# Battery_board_V4_1.net
KiCad netlist of a schematic drawn in EAGLE
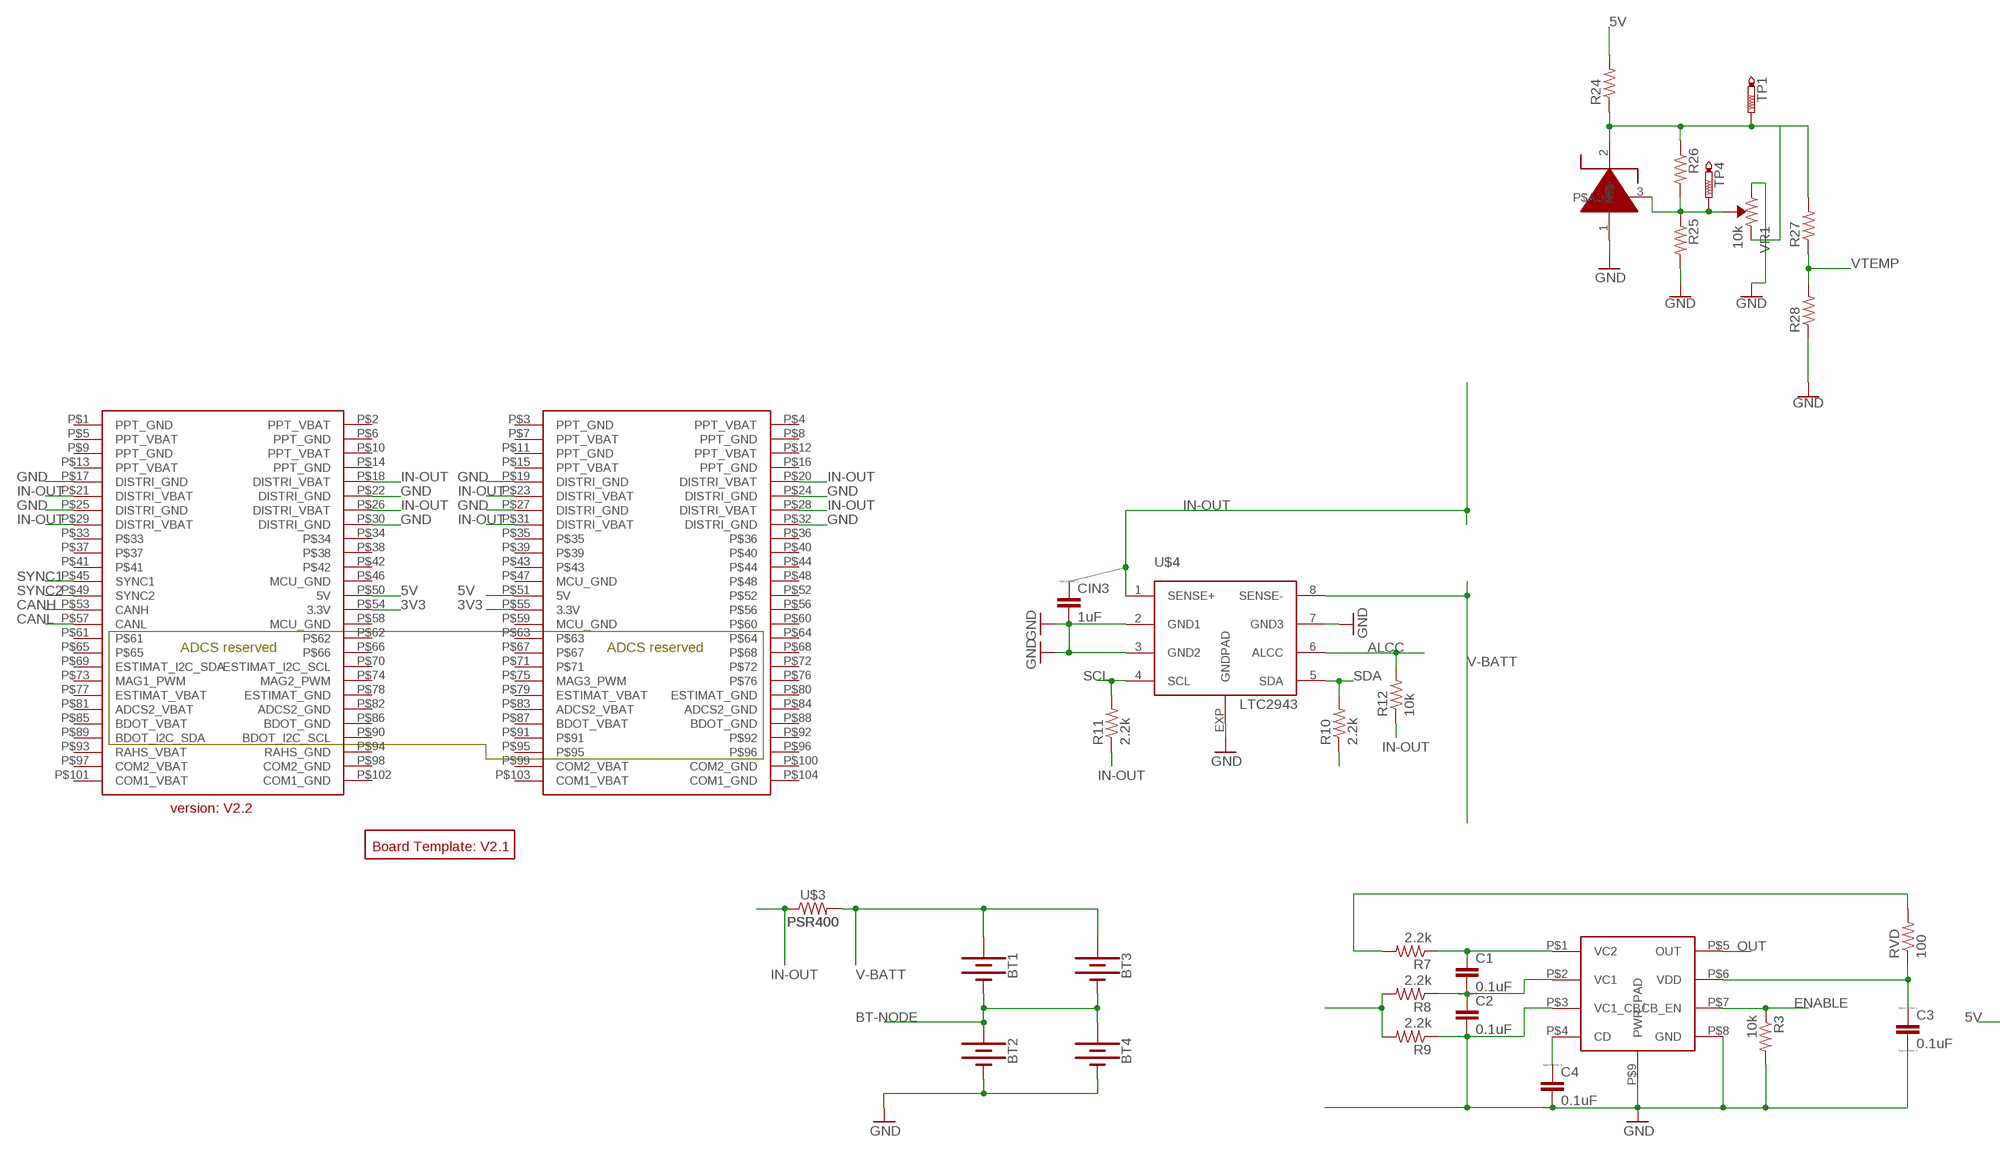
[diagram p0: schematic, sheet 1, part 1 of 2]
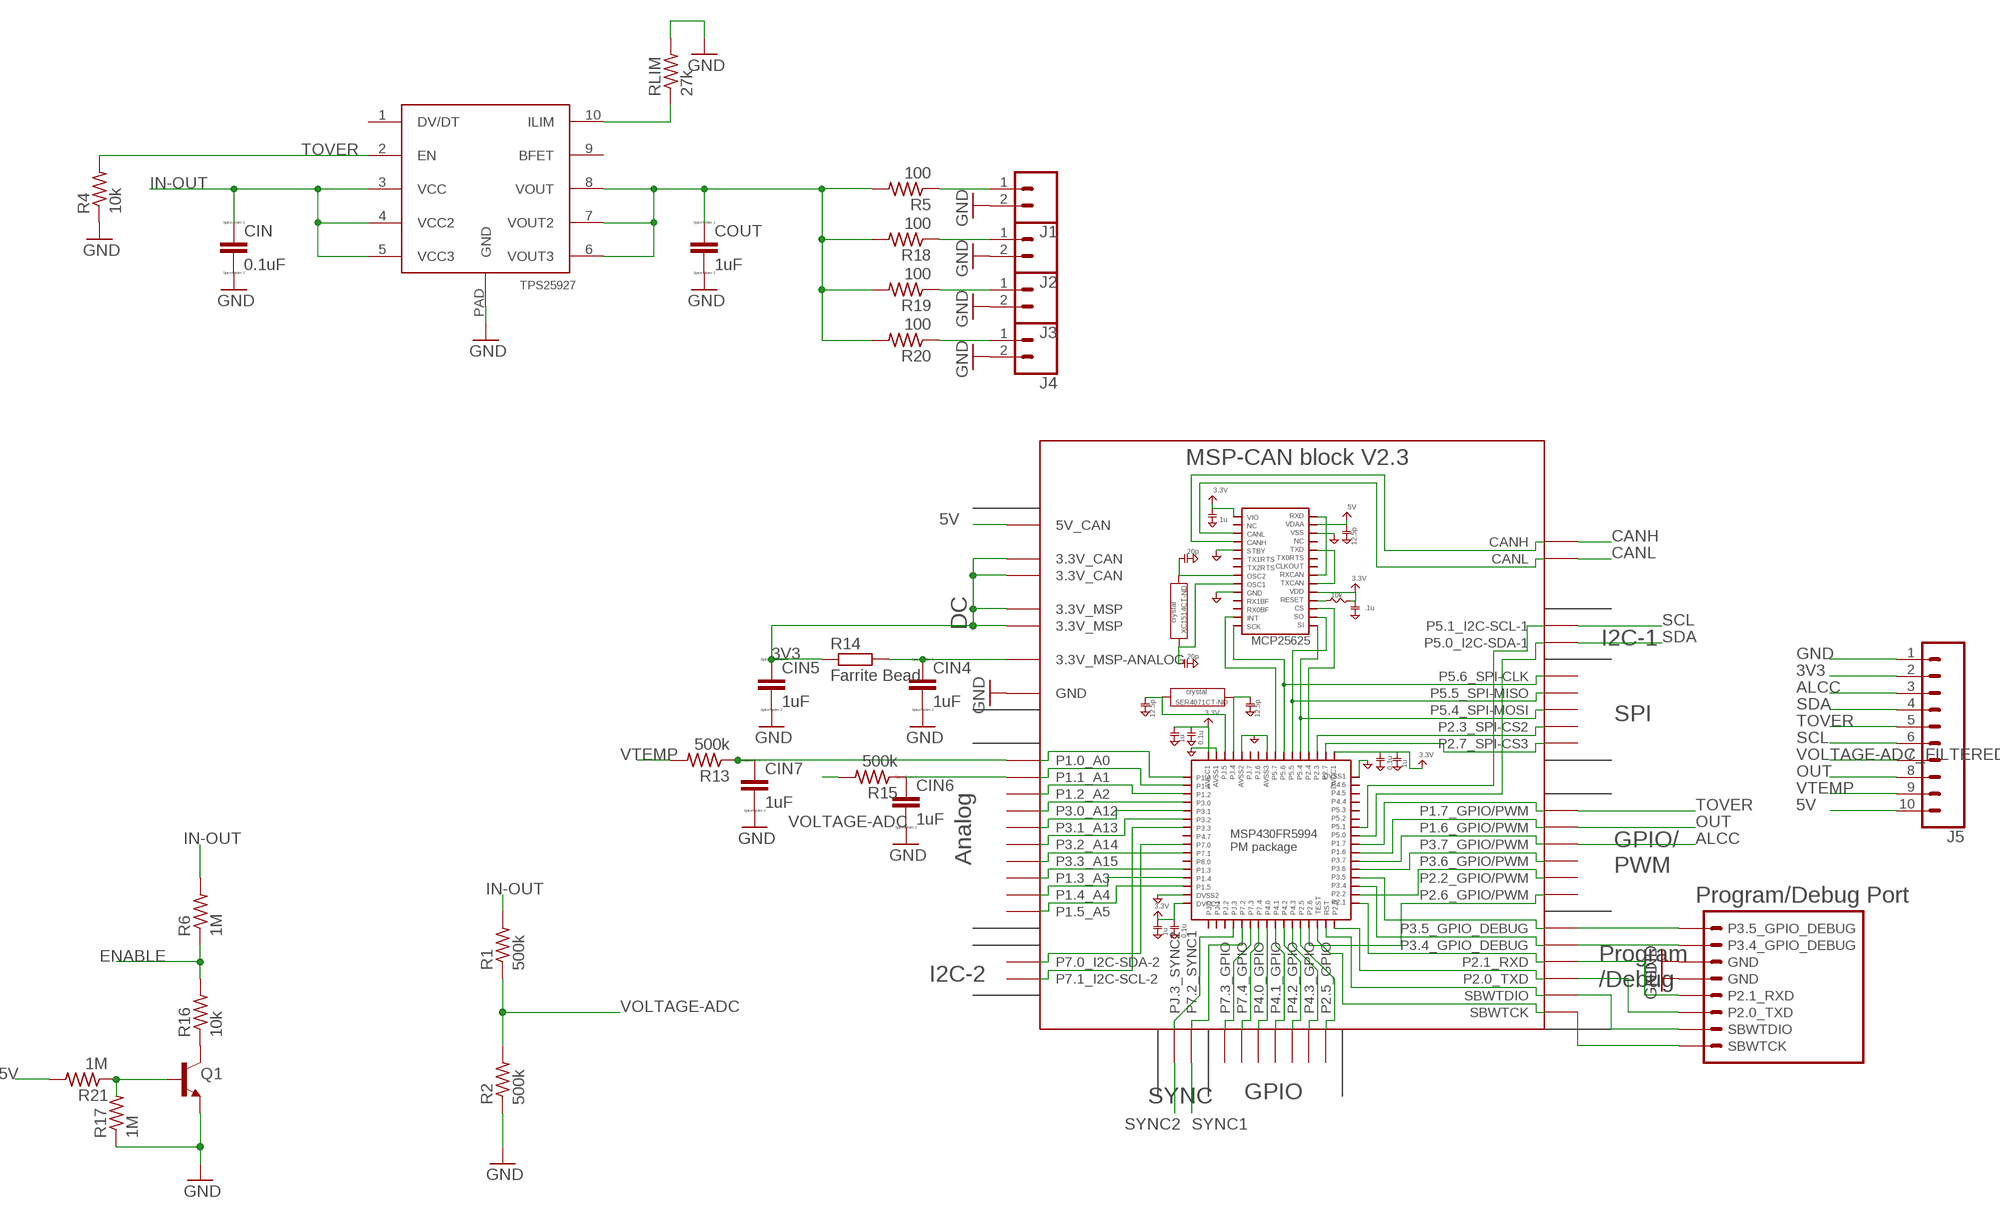
[diagram p1: schematic, sheet 1, part 2 of 2]

(export (version "E")
  (design (tool "Eeschema 10.0.6"))
  (components
    (comp (ref "BT1")
      (value "BATTERY-18650")
      (footprint "eagle-import:BATTERY_18650-HOLDER")
      (libsource (lib "eagle-import") (part "BATTERY-18650"))
    )
    (comp (ref "BT2")
      (value "BATTERY-18650")
      (footprint "eagle-import:BATTERY_18650-HOLDER")
      (libsource (lib "eagle-import") (part "BATTERY-18650"))
    )
    (comp (ref "BT3")
      (value "BATTERY-18650")
      (footprint "eagle-import:BATTERY_18650-HOLDER")
      (libsource (lib "eagle-import") (part "BATTERY-18650"))
    )
    (comp (ref "BT4")
      (value "BATTERY-18650")
      (footprint "eagle-import:BATTERY_18650-HOLDER")
      (libsource (lib "eagle-import") (part "BATTERY-18650"))
    )
    (comp (ref "C1")
      (value "0.1uF")
      (footprint "eagle-import:C0805")
      (libsource (lib "eagle-import") (part "C"))
    )
    (comp (ref "C2")
      (value "0.1uF")
      (footprint "eagle-import:C0805")
      (libsource (lib "eagle-import") (part "C"))
    )
    (comp (ref "C3")
      (value "0.1uF")
      (footprint "eagle-import:C0805")
      (libsource (lib "eagle-import") (part "C"))
    )
    (comp (ref "C4")
      (value "0.1uF")
      (footprint "eagle-import:C0805")
      (libsource (lib "eagle-import") (part "C"))
    )
    (comp (ref "CIN")
      (value "0.1uF")
      (footprint "eagle-import:C0805")
      (libsource (lib "eagle-import") (part "C"))
    )
    (comp (ref "CIN3")
      (value "1uF")
      (footprint "eagle-import:C0805")
      (libsource (lib "eagle-import") (part "C"))
    )
    (comp (ref "CIN4")
      (value "1uF")
      (footprint "eagle-import:C0805")
      (libsource (lib "eagle-import") (part "C"))
    )
    (comp (ref "CIN5")
      (value "1uF")
      (footprint "eagle-import:C0805")
      (libsource (lib "eagle-import") (part "C"))
    )
    (comp (ref "CIN6")
      (value "1uF")
      (footprint "eagle-import:C0805")
      (libsource (lib "eagle-import") (part "C"))
    )
    (comp (ref "CIN7")
      (value "1uF")
      (footprint "eagle-import:C0805")
      (libsource (lib "eagle-import") (part "C"))
    )
    (comp (ref "COUT")
      (value "1uF")
      (footprint "eagle-import:C0805")
      (libsource (lib "eagle-import") (part "C"))
    )
    (comp (ref "J1")
      (value "CONN_02PTH3")
      (footprint "eagle-import:1X02_LONGPADS")
      (libsource (lib "eagle-import") (part "CONN_02PTH3"))
    )
    (comp (ref "J2")
      (value "CONN_02PTH3")
      (footprint "eagle-import:1X02_LONGPADS")
      (libsource (lib "eagle-import") (part "CONN_02PTH3"))
    )
    (comp (ref "J3")
      (value "CONN_02PTH3")
      (footprint "eagle-import:1X02_LONGPADS")
      (libsource (lib "eagle-import") (part "CONN_02PTH3"))
    )
    (comp (ref "J4")
      (value "CONN_02PTH3")
      (footprint "eagle-import:1X02_LONGPADS")
      (libsource (lib "eagle-import") (part "CONN_02PTH3"))
    )
    (comp (ref "J5")
      (value "CONN_10LOCK")
      (footprint "eagle-import:1X10_LOCK")
      (libsource (lib "eagle-import") (part "CONN_10LOCK"))
    )
    (comp (ref "Q1")
      (value "TRANS_NPN-MMBT2222AL")
      (footprint "eagle-import:SOT23-3")
      (libsource (lib "eagle-import") (part "TRANS_NPN-MMBT2222AL"))
    )
    (comp (ref "R1")
      (value "500k")
      (footprint "eagle-import:R0805")
      (libsource (lib "eagle-import") (part "R-US_R0805"))
    )
    (comp (ref "R2")
      (value "500k")
      (footprint "eagle-import:R0805")
      (libsource (lib "eagle-import") (part "R-US_R0805"))
    )
    (comp (ref "R3")
      (value "10k")
      (footprint "eagle-import:R0805")
      (libsource (lib "eagle-import") (part "R-US_R0805"))
    )
    (comp (ref "R4")
      (value "10k")
      (footprint "eagle-import:R0805")
      (libsource (lib "eagle-import") (part "R-US_R0805"))
    )
    (comp (ref "R5")
      (value "100")
      (footprint "eagle-import:R0805")
      (libsource (lib "eagle-import") (part "R-US_R0805"))
    )
    (comp (ref "R6")
      (value "1M")
      (footprint "eagle-import:R0805")
      (libsource (lib "eagle-import") (part "R-US_R0805"))
    )
    (comp (ref "R7")
      (value "2.2k")
      (footprint "eagle-import:R0805")
      (libsource (lib "eagle-import") (part "R-US_R0805"))
    )
    (comp (ref "R8")
      (value "2.2k")
      (footprint "eagle-import:R0805")
      (libsource (lib "eagle-import") (part "R-US_R0805"))
    )
    (comp (ref "R9")
      (value "2.2k")
      (footprint "eagle-import:R0805")
      (libsource (lib "eagle-import") (part "R-US_R0805"))
    )
    (comp (ref "R10")
      (value "2.2k")
      (footprint "eagle-import:R0805")
      (libsource (lib "eagle-import") (part "R-US_R0805"))
    )
    (comp (ref "R11")
      (value "2.2k")
      (footprint "eagle-import:R0805")
      (libsource (lib "eagle-import") (part "R-US_R0805"))
    )
    (comp (ref "R12")
      (value "10k")
      (footprint "eagle-import:R0805")
      (libsource (lib "eagle-import") (part "R-US_R0805"))
    )
    (comp (ref "R13")
      (value "500k")
      (footprint "eagle-import:R0805")
      (libsource (lib "eagle-import") (part "R-US_R0805"))
    )
    (comp (ref "R14")
      (value "Farrite Bead")
      (footprint "eagle-import:R1206")
      (libsource (lib "eagle-import") (part "R-EU_R1206"))
    )
    (comp (ref "R15")
      (value "500k")
      (footprint "eagle-import:R0805")
      (libsource (lib "eagle-import") (part "R-US_R0805"))
    )
    (comp (ref "R16")
      (value "10k")
      (footprint "eagle-import:R0805")
      (libsource (lib "eagle-import") (part "R-US_R0805"))
    )
    (comp (ref "R17")
      (value "1M")
      (footprint "eagle-import:M0805")
      (libsource (lib "eagle-import") (part "R-US_M0805"))
    )
    (comp (ref "R18")
      (value "100")
      (footprint "eagle-import:R0805")
      (libsource (lib "eagle-import") (part "R-US_R0805"))
    )
    (comp (ref "R19")
      (value "100")
      (footprint "eagle-import:R0805")
      (libsource (lib "eagle-import") (part "R-US_R0805"))
    )
    (comp (ref "R20")
      (value "100")
      (footprint "eagle-import:R0805")
      (libsource (lib "eagle-import") (part "R-US_R0805"))
    )
    (comp (ref "R21")
      (value "1M")
      (footprint "eagle-import:M0805")
      (libsource (lib "eagle-import") (part "R-US_M0805"))
    )
    (comp (ref "R24")
      (value "R-US_R0805")
      (footprint "eagle-import:R0805")
      (libsource (lib "eagle-import") (part "R-US_R0805"))
    )
    (comp (ref "R25")
      (value "R-US_R0805")
      (footprint "eagle-import:R0805")
      (libsource (lib "eagle-import") (part "R-US_R0805"))
    )
    (comp (ref "R26")
      (value "R-US_R0805")
      (footprint "eagle-import:R0805")
      (libsource (lib "eagle-import") (part "R-US_R0805"))
    )
    (comp (ref "R27")
      (value "R-US_R0805")
      (footprint "eagle-import:R0805")
      (libsource (lib "eagle-import") (part "R-US_R0805"))
    )
    (comp (ref "R28")
      (value "R-US_R0805")
      (footprint "eagle-import:R0805")
      (libsource (lib "eagle-import") (part "R-US_R0805"))
    )
    (comp (ref "RLIM")
      (value "27k")
      (footprint "eagle-import:R0805")
      (libsource (lib "eagle-import") (part "R-US_R0805"))
    )
    (comp (ref "RVD")
      (value "100")
      (footprint "eagle-import:R0805")
      (libsource (lib "eagle-import") (part "R-US_R0805"))
    )
    (comp (ref "TP1")
      (value "PTR1PAD1-13Y")
      (footprint "eagle-import:P1-13Y")
      (libsource (lib "eagle-import") (part "PTR1PAD1-13Y"))
    )
    (comp (ref "TP4")
      (value "PTR1PAD1-13Y")
      (footprint "eagle-import:P1-13Y")
      (libsource (lib "eagle-import") (part "PTR1PAD1-13Y"))
    )
    (comp (ref "U$1")
      (value "MSP-CAN_BLOCK")
      (footprint "eagle-import:MSP-CAN_BLOCK")
      (libsource (lib "eagle-import") (part "MSP-CAN_BLOCK"))
    )
    (comp (ref "U$2")
      (value "PROGRAM/DEBUG_PORT")
      (footprint "eagle-import:1X08_CONNECTOR")
      (libsource (lib "eagle-import") (part "PROGRAM/DEBUG_PORT"))
    )
    (comp (ref "U$3")
      (value "PSR400")
      (footprint "eagle-import:PSR400")
      (libsource (lib "eagle-import") (part "PSR400"))
    )
    (comp (ref "U$4")
      (value "LTC2943")
      (footprint "eagle-import:DFN8(3X3)LT")
      (libsource (lib "eagle-import") (part "LTC2943"))
    )
    (comp (ref "U$5")
      (value "TPS252927")
      (footprint "eagle-import:VSON10")
      (libsource (lib "eagle-import") (part "TPS252927"))
    )
    (comp (ref "U$7")
      (value "2X26_CONNECTOR_(V2.2)")
      (footprint "eagle-import:4X26_CONNECTOR_(V2.2)")
      (libsource (lib "eagle-import") (part "2X26_CONNECTOR_(V2.2)"))
    )
    (comp (ref "U$8")
      (value "BQ29209")
      (footprint "eagle-import:VSON8")
      (libsource (lib "eagle-import") (part "BQ29209"))
    )
    (comp (ref "U$9")
      (value "BOARD_TEMPLATE_(V2.1)")
      (footprint "eagle-import:BOARD_TEMPLATE_(V2.1)")
      (libsource (lib "eagle-import") (part "BOARD_TEMPLATE_(V2.1)"))
    )
    (comp (ref "U$10")
      (value "LM135Z")
      (footprint "eagle-import:TO-92-3")
      (libsource (lib "eagle-import") (part "LM135Z"))
    )
    (comp (ref "VR1")
      (value "10k")
      (footprint "eagle-import:TRIMPOT-SMD-TC33X")
      (libsource (lib "eagle-import") (part "TRIMPOT-SMD-3MM-OPEN-1/10W-25%"))
    )
  )
  (nets
    (net (code "1") (name "/3V3") (class "Default")
      (node (ref "CIN5") (pin "1") (pinfunction "1_1") (pintype "passive"))
      (node (ref "J5") (pin "2") (pinfunction "2_2") (pintype "passive"))
      (node (ref "R14") (pin "1") (pinfunction "1_1") (pintype "passive"))
      (node (ref "U$1") (pin "3.3V@CAN1") (pinfunction "3.3V_CAN_3.3V@CAN1") (pintype "bidirectional"))
      (node (ref "U$1") (pin "3.3V@CAN2") (pinfunction "3.3V_CAN_3.3V@CAN2") (pintype "bidirectional"))
      (node (ref "U$1") (pin "3.3V@MSP1") (pinfunction "3.3V_MSP_3.3V@MSP1") (pintype "bidirectional"))
      (node (ref "U$1") (pin "3.3V@MSP2") (pinfunction "3.3V_MSP_3.3V@MSP2") (pintype "bidirectional"))
      (node (ref "U$7") (pin "P$54") (pinfunction "3.3V_P$54") (pintype "bidirectional"))
      (node (ref "U$7") (pin "P$55") (pinfunction "3.3V_P$55") (pintype "bidirectional"))
    )
    (net (code "2") (name "/5V") (class "Default")
      (node (ref "J5") (pin "10") (pinfunction "10_10") (pintype "passive"))
      (node (ref "R21") (pin "2") (pinfunction "2_2") (pintype "passive"))
      (node (ref "R24") (pin "2") (pinfunction "2_2") (pintype "passive"))
      (node (ref "U$1") (pin "5V") (pinfunction "5V_CAN_5V") (pintype "bidirectional"))
      (node (ref "U$7") (pin "P$50") (pinfunction "5V_P$50") (pintype "bidirectional"))
      (node (ref "U$7") (pin "P$51") (pinfunction "5V_P$51") (pintype "bidirectional"))
    )
    (net (code "3") (name "/ALCC") (class "Default")
      (node (ref "J5") (pin "3") (pinfunction "3_3") (pintype "passive"))
      (node (ref "R12") (pin "2") (pinfunction "2_2") (pintype "passive"))
      (node (ref "U$1") (pin "P3.7_GPIO/PWM") (pinfunction "P3.7_GPIO/PWM_P3.7_GPIO/PWM") (pintype "bidirectional"))
      (node (ref "U$4") (pin "6") (pinfunction "ALCC_6") (pintype "bidirectional"))
    )
    (net (code "4") (name "/BT-NODE") (class "Default")
      (node (ref "BT1") (pin "GND@1") (pinfunction "-_GND@1") (pintype "power_in"))
      (node (ref "BT2") (pin "PWR@1") (pinfunction "+_PWR@1") (pintype "power_in"))
      (node (ref "BT3") (pin "GND@1") (pinfunction "-_GND@1") (pintype "power_in"))
      (node (ref "BT4") (pin "PWR@1") (pinfunction "+_PWR@1") (pintype "power_in"))
      (node (ref "R8") (pin "2") (pinfunction "2_2") (pintype "passive"))
      (node (ref "R9") (pin "2") (pinfunction "2_2") (pintype "passive"))
    )
    (net (code "5") (name "/CANH") (class "Default")
      (node (ref "U$1") (pin "CANH") (pinfunction "CANH_CANH") (pintype "bidirectional"))
      (node (ref "U$7") (pin "P$53") (pinfunction "CANH_P$53") (pintype "bidirectional"))
    )
    (net (code "6") (name "/CANL") (class "Default")
      (node (ref "U$1") (pin "CANL") (pinfunction "CANL_CANL") (pintype "bidirectional"))
      (node (ref "U$7") (pin "P$57") (pinfunction "CANL_P$57") (pintype "bidirectional"))
    )
    (net (code "7") (name "/ENABLE") (class "Default")
      (node (ref "R16") (pin "2") (pinfunction "2_2") (pintype "passive"))
      (node (ref "R3") (pin "1") (pinfunction "1_1") (pintype "passive"))
      (node (ref "R6") (pin "1") (pinfunction "1_1") (pintype "passive"))
      (node (ref "U$8") (pin "P$7") (pinfunction "CB_EN_P$7") (pintype "bidirectional"))
    )
    (net (code "8") (name "/IN-OUT") (class "Default")
      (node (ref "CIN") (pin "1") (pinfunction "1_1") (pintype "passive"))
      (node (ref "CIN3") (pin "1") (pinfunction "1_1") (pintype "passive"))
      (node (ref "R1") (pin "2") (pinfunction "2_2") (pintype "passive"))
      (node (ref "R10") (pin "1") (pinfunction "1_1") (pintype "passive"))
      (node (ref "R11") (pin "1") (pinfunction "1_1") (pintype "passive"))
      (node (ref "R12") (pin "1") (pinfunction "1_1") (pintype "passive"))
      (node (ref "R6") (pin "2") (pinfunction "2_2") (pintype "passive"))
      (node (ref "R7") (pin "2") (pinfunction "2_2") (pintype "passive"))
      (node (ref "RVD") (pin "2") (pinfunction "2_2") (pintype "passive"))
      (node (ref "U$3") (pin "P$1") (pinfunction "1_P$1") (pintype "passive"))
      (node (ref "U$4") (pin "1") (pinfunction "SENSE+_1") (pintype "bidirectional"))
      (node (ref "U$5") (pin "3") (pinfunction "VCC_3") (pintype "bidirectional"))
      (node (ref "U$5") (pin "4") (pinfunction "VCC2_4") (pintype "bidirectional"))
      (node (ref "U$5") (pin "5") (pinfunction "VCC3_5") (pintype "bidirectional"))
      (node (ref "U$7") (pin "P$18") (pinfunction "DISTRI_VBAT_P$18") (pintype "bidirectional"))
      (node (ref "U$7") (pin "P$20") (pinfunction "DISTRI_VBAT_P$20") (pintype "bidirectional"))
      (node (ref "U$7") (pin "P$21") (pinfunction "DISTRI_VBAT_P$21") (pintype "bidirectional"))
      (node (ref "U$7") (pin "P$23") (pinfunction "DISTRI_VBAT_P$23") (pintype "bidirectional"))
      (node (ref "U$7") (pin "P$26") (pinfunction "DISTRI_VBAT_P$26") (pintype "bidirectional"))
      (node (ref "U$7") (pin "P$28") (pinfunction "DISTRI_VBAT_P$28") (pintype "bidirectional"))
      (node (ref "U$7") (pin "P$29") (pinfunction "DISTRI_VBAT_P$29") (pintype "bidirectional"))
      (node (ref "U$7") (pin "P$31") (pinfunction "DISTRI_VBAT_P$31") (pintype "bidirectional"))
    )
    (net (code "9") (name "/OUT") (class "Default")
      (node (ref "J5") (pin "8") (pinfunction "8_8") (pintype "passive"))
      (node (ref "U$1") (pin "P1.6_GPIO/PWM") (pinfunction "P1.6_GPIO/PWM_P1.6_GPIO/PWM") (pintype "bidirectional"))
      (node (ref "U$8") (pin "P$5") (pinfunction "OUT_P$5") (pintype "bidirectional"))
    )
    (net (code "10") (name "/SCL") (class "Default")
      (node (ref "J5") (pin "6") (pinfunction "6_6") (pintype "passive"))
      (node (ref "R11") (pin "2") (pinfunction "2_2") (pintype "passive"))
      (node (ref "U$1") (pin "P5.1_I2C-SCL-1") (pinfunction "P5.1_I2C-SCL-1_P5.1_I2C-SCL-1") (pintype "bidirectional"))
      (node (ref "U$4") (pin "4") (pinfunction "SCL_4") (pintype "bidirectional"))
    )
    (net (code "11") (name "/SDA") (class "Default")
      (node (ref "J5") (pin "4") (pinfunction "4_4") (pintype "passive"))
      (node (ref "R10") (pin "2") (pinfunction "2_2") (pintype "passive"))
      (node (ref "U$1") (pin "P5.0_I2C-SDA-1") (pinfunction "P5.0_I2C-SDA-1_P5.0_I2C-SDA-1") (pintype "bidirectional"))
      (node (ref "U$4") (pin "5") (pinfunction "SDA_5") (pintype "bidirectional"))
    )
    (net (code "12") (name "/SYNC1") (class "Default")
      (node (ref "U$1") (pin "P7.2_SYNC1") (pinfunction "P7.2_SYNC1_P7.2_SYNC1") (pintype "bidirectional"))
      (node (ref "U$7") (pin "P$45") (pinfunction "SYNC1_P$45") (pintype "bidirectional"))
    )
    (net (code "13") (name "/SYNC2") (class "Default")
      (node (ref "U$1") (pin "PJ.3_SYNC2") (pinfunction "PJ.3_SYNC2_PJ.3_SYNC2") (pintype "bidirectional"))
      (node (ref "U$7") (pin "P$49") (pinfunction "SYNC2_P$49") (pintype "bidirectional"))
    )
    (net (code "14") (name "/TOVER") (class "Default")
      (node (ref "J5") (pin "5") (pinfunction "5_5") (pintype "passive"))
      (node (ref "R4") (pin "2") (pinfunction "2_2") (pintype "passive"))
      (node (ref "U$1") (pin "P1.7_GPIO/PWM") (pinfunction "P1.7_GPIO/PWM_P1.7_GPIO/PWM") (pintype "bidirectional"))
      (node (ref "U$5") (pin "2") (pinfunction "EN_2") (pintype "bidirectional"))
    )
    (net (code "15") (name "/V-BATT") (class "Default")
      (node (ref "BT1") (pin "PWR@1") (pinfunction "+_PWR@1") (pintype "power_in"))
      (node (ref "BT3") (pin "PWR@1") (pinfunction "+_PWR@1") (pintype "power_in"))
      (node (ref "U$3") (pin "P$2") (pinfunction "2_P$2") (pintype "passive"))
      (node (ref "U$4") (pin "8") (pinfunction "SENSE-_8") (pintype "bidirectional"))
    )
    (net (code "16") (name "/VOLTAGE-ADC") (class "Default")
      (node (ref "R1") (pin "1") (pinfunction "1_1") (pintype "passive"))
      (node (ref "R15") (pin "2") (pinfunction "2_2") (pintype "passive"))
      (node (ref "R2") (pin "2") (pinfunction "2_2") (pintype "passive"))
    )
    (net (code "17") (name "/VOLTAGE-ADC_FILTERED") (class "Default")
      (node (ref "CIN6") (pin "1") (pinfunction "1_1") (pintype "passive"))
      (node (ref "J5") (pin "7") (pinfunction "7_7") (pintype "passive"))
      (node (ref "R15") (pin "1") (pinfunction "1_1") (pintype "passive"))
      (node (ref "U$1") (pin "P1.1_A1") (pinfunction "P1.1_A1_P1.1_A1") (pintype "bidirectional"))
    )
    (net (code "18") (name "/VTEMP") (class "Default")
      (node (ref "J5") (pin "9") (pinfunction "9_9") (pintype "passive"))
      (node (ref "R13") (pin "2") (pinfunction "2_2") (pintype "passive"))
      (node (ref "R27") (pin "1") (pinfunction "1_1") (pintype "passive"))
      (node (ref "R28") (pin "2") (pinfunction "2_2") (pintype "passive"))
    )
    (net (code "19") (name "GND") (class "Default")
      (node (ref "BT2") (pin "GND@1") (pinfunction "-_GND@1") (pintype "power_in"))
      (node (ref "BT4") (pin "GND@1") (pinfunction "-_GND@1") (pintype "power_in"))
      (node (ref "C2") (pin "2") (pinfunction "2_2") (pintype "passive"))
      (node (ref "C3") (pin "2") (pinfunction "2_2") (pintype "passive"))
      (node (ref "C4") (pin "2") (pinfunction "2_2") (pintype "passive"))
      (node (ref "CIN") (pin "2") (pinfunction "2_2") (pintype "passive"))
      (node (ref "CIN3") (pin "2") (pinfunction "2_2") (pintype "passive"))
      (node (ref "CIN4") (pin "2") (pinfunction "2_2") (pintype "passive"))
      (node (ref "CIN5") (pin "2") (pinfunction "2_2") (pintype "passive"))
      (node (ref "CIN6") (pin "2") (pinfunction "2_2") (pintype "passive"))
      (node (ref "CIN7") (pin "2") (pinfunction "2_2") (pintype "passive"))
      (node (ref "COUT") (pin "2") (pinfunction "2_2") (pintype "passive"))
      (node (ref "J1") (pin "2") (pinfunction "2_2") (pintype "passive"))
      (node (ref "J2") (pin "2") (pinfunction "2_2") (pintype "passive"))
      (node (ref "J3") (pin "2") (pinfunction "2_2") (pintype "passive"))
      (node (ref "J4") (pin "2") (pinfunction "2_2") (pintype "passive"))
      (node (ref "J5") (pin "1") (pinfunction "1_1") (pintype "passive"))
      (node (ref "Q1") (pin "2") (pinfunction "E_2") (pintype "passive"))
      (node (ref "R17") (pin "1") (pinfunction "1_1") (pintype "passive"))
      (node (ref "R2") (pin "1") (pinfunction "1_1") (pintype "passive"))
      (node (ref "R25") (pin "2") (pinfunction "2_2") (pintype "passive"))
      (node (ref "R28") (pin "1") (pinfunction "1_1") (pintype "passive"))
      (node (ref "R3") (pin "2") (pinfunction "2_2") (pintype "passive"))
      (node (ref "R4") (pin "1") (pinfunction "1_1") (pintype "passive"))
      (node (ref "R9") (pin "1") (pinfunction "1_1") (pintype "passive"))
      (node (ref "RLIM") (pin "2") (pinfunction "2_2") (pintype "passive"))
      (node (ref "U$1") (pin "GND@1") (pinfunction "GND_GND@1") (pintype "bidirectional"))
      (node (ref "U$1") (pin "GND@10") (pinfunction "GND_GND@10") (pintype "bidirectional"))
      (node (ref "U$1") (pin "GND@11") (pinfunction "GND_GND@11") (pintype "bidirectional"))
      (node (ref "U$1") (pin "GND@12") (pinfunction "GND_GND@12") (pintype "bidirectional"))
      (node (ref "U$1") (pin "GND@13") (pinfunction "GND_GND@13") (pintype "bidirectional"))
      (node (ref "U$1") (pin "GND@14") (pinfunction "GND_GND@14") (pintype "bidirectional"))
      (node (ref "U$1") (pin "GND@15") (pinfunction "GND_GND@15") (pintype "bidirectional"))
      (node (ref "U$1") (pin "GND@16") (pinfunction "GND_GND@16") (pintype "bidirectional"))
      (node (ref "U$1") (pin "GND@17") (pinfunction "GND_GND@17") (pintype "bidirectional"))
      (node (ref "U$1") (pin "GND@2") (pinfunction "GND_GND@2") (pintype "bidirectional"))
      (node (ref "U$1") (pin "GND@26") (pinfunction "GND_GND@26") (pintype "bidirectional"))
      (node (ref "U$1") (pin "GND@3") (pinfunction "GND_GND@3") (pintype "bidirectional"))
      (node (ref "U$1") (pin "GND@4") (pinfunction "GND_GND@4") (pintype "bidirectional"))
      (node (ref "U$1") (pin "GND@5") (pinfunction "GND_GND@5") (pintype "bidirectional"))
      (node (ref "U$1") (pin "GND@7") (pinfunction "GND_GND@7") (pintype "bidirectional"))
      (node (ref "U$1") (pin "GND@8") (pinfunction "GND_GND@8") (pintype "bidirectional"))
      (node (ref "U$1") (pin "GND@9") (pinfunction "GND_GND@9") (pintype "bidirectional"))
      (node (ref "U$10") (pin "1") (pinfunction "P$-_1") (pintype "bidirectional"))
      (node (ref "U$2") (pin "5") (pinfunction "GND_5") (pintype "bidirectional"))
      (node (ref "U$2") (pin "6") (pinfunction "GND_6") (pintype "bidirectional"))
      (node (ref "U$4") (pin "2") (pinfunction "GND1_2") (pintype "bidirectional"))
      (node (ref "U$4") (pin "3") (pinfunction "GND2_3") (pintype "bidirectional"))
      (node (ref "U$4") (pin "7") (pinfunction "GND3_7") (pintype "bidirectional"))
      (node (ref "U$4") (pin "EXP") (pinfunction "GNDPAD_EXP") (pintype "bidirectional"))
      (node (ref "U$5") (pin "PAD") (pinfunction "GND_PAD") (pintype "bidirectional"))
      (node (ref "U$7") (pin "P$17") (pinfunction "DISTRI_GND_P$17") (pintype "bidirectional"))
      (node (ref "U$7") (pin "P$19") (pinfunction "DISTRI_GND_P$19") (pintype "bidirectional"))
      (node (ref "U$7") (pin "P$22") (pinfunction "DISTRI_GND_P$22") (pintype "bidirectional"))
      (node (ref "U$7") (pin "P$24") (pinfunction "DISTRI_GND_P$24") (pintype "bidirectional"))
      (node (ref "U$7") (pin "P$25") (pinfunction "DISTRI_GND_P$25") (pintype "bidirectional"))
      (node (ref "U$7") (pin "P$27") (pinfunction "DISTRI_GND_P$27") (pintype "bidirectional"))
      (node (ref "U$7") (pin "P$30") (pinfunction "DISTRI_GND_P$30") (pintype "bidirectional"))
      (node (ref "U$7") (pin "P$32") (pinfunction "DISTRI_GND_P$32") (pintype "bidirectional"))
      (node (ref "U$8") (pin "P$3") (pinfunction "VC1_CB_P$3") (pintype "bidirectional"))
      (node (ref "U$8") (pin "P$8") (pinfunction "GND_P$8") (pintype "bidirectional"))
      (node (ref "U$8") (pin "P$9") (pinfunction "PWR_PAD_P$9") (pintype "bidirectional"))
      (node (ref "VR1") (pin "1") (pinfunction "CW_1") (pintype "passive"))
    )
    (net (code "20") (name "Net-(CIN7-Pad1)") (class "Default")
      (node (ref "CIN7") (pin "1") (pinfunction "1_1") (pintype "passive"))
      (node (ref "R13") (pin "1") (pinfunction "1_1") (pintype "passive"))
      (node (ref "U$1") (pin "P1.0_A0") (pinfunction "P1.0_A0_P1.0_A0") (pintype "bidirectional"))
    )
    (net (code "21") (name "Net-(J1-Pad1)") (class "Default")
      (node (ref "J1") (pin "1") (pinfunction "1_1") (pintype "passive"))
      (node (ref "R5") (pin "1") (pinfunction "1_1") (pintype "passive"))
    )
    (net (code "22") (name "Net-(J2-Pad1)") (class "Default")
      (node (ref "J2") (pin "1") (pinfunction "1_1") (pintype "passive"))
      (node (ref "R18") (pin "1") (pinfunction "1_1") (pintype "passive"))
    )
    (net (code "23") (name "Net-(J3-Pad1)") (class "Default")
      (node (ref "J3") (pin "1") (pinfunction "1_1") (pintype "passive"))
      (node (ref "R19") (pin "1") (pinfunction "1_1") (pintype "passive"))
    )
    (net (code "24") (name "Net-(J4-Pad1)") (class "Default")
      (node (ref "J4") (pin "1") (pinfunction "1_1") (pintype "passive"))
      (node (ref "R20") (pin "1") (pinfunction "1_1") (pintype "passive"))
    )
    (net (code "25") (name "Net-(Q1-B)") (class "Default")
      (node (ref "Q1") (pin "1") (pinfunction "B_1") (pintype "passive"))
      (node (ref "R17") (pin "2") (pinfunction "2_2") (pintype "passive"))
      (node (ref "R21") (pin "1") (pinfunction "1_1") (pintype "passive"))
    )
    (net (code "26") (name "Net-(Q1-C)") (class "Default")
      (node (ref "Q1") (pin "3") (pinfunction "C_3") (pintype "passive"))
      (node (ref "R16") (pin "1") (pinfunction "1_1") (pintype "passive"))
    )
    (net (code "27") (name "Net-(U$1-3.3V_MSP-ANALOG)") (class "Default")
      (node (ref "CIN4") (pin "1") (pinfunction "1_1") (pintype "passive"))
      (node (ref "R14") (pin "2") (pinfunction "2_2") (pintype "passive"))
      (node (ref "U$1") (pin "3.3V_ANALOG@MSP2") (pinfunction "3.3V_MSP-ANALOG_3.3V_ANALOG@MSP2") (pintype "bidirectional"))
    )
    (net (code "28") (name "Net-(U$1-PadSBWTCK)") (class "Default")
      (node (ref "U$1") (pin "SBWTCK") (pinfunction "SBWTCK_SBWTCK") (pintype "bidirectional"))
      (node (ref "U$2") (pin "SBWTCK") (pinfunction "SBWTCK_SBWTCK") (pintype "bidirectional"))
    )
    (net (code "29") (name "Net-(U$2-P2.0_TXD)") (class "Default")
      (node (ref "U$1") (pin "P2.0_TXD") (pinfunction "P2.0_TXD_P2.0_TXD") (pintype "bidirectional"))
      (node (ref "U$2") (pin "3") (pinfunction "P2.0_TXD_3") (pintype "bidirectional"))
    )
    (net (code "30") (name "Net-(U$2-P2.1_RXD)") (class "Default")
      (node (ref "U$1") (pin "P2.1_RXD") (pinfunction "P2.1_RXD_P2.1_RXD") (pintype "bidirectional"))
      (node (ref "U$2") (pin "4") (pinfunction "P2.1_RXD_4") (pintype "bidirectional"))
    )
    (net (code "31") (name "Net-(U$2-P3.4_GPIO_DEBUG)") (class "Default")
      (node (ref "U$1") (pin "P3.4_GPIO_DEBUG") (pinfunction "P3.4_GPIO_DEBUG_P3.4_GPIO_DEBUG") (pintype "bidirectional"))
      (node (ref "U$2") (pin "7") (pinfunction "P3.4_GPIO_DEBUG_7") (pintype "bidirectional"))
    )
    (net (code "32") (name "Net-(U$2-P3.5_GPIO_DEBUG)") (class "Default")
      (node (ref "U$1") (pin "P3.5_GPIO_DEBUG") (pinfunction "P3.5_GPIO_DEBUG_P3.5_GPIO_DEBUG") (pintype "bidirectional"))
      (node (ref "U$2") (pin "8") (pinfunction "P3.5_GPIO_DEBUG_8") (pintype "bidirectional"))
    )
    (net (code "33") (name "Net-(U$2-SBWTDIO)") (class "Default")
      (node (ref "U$1") (pin "SBWTDIO") (pinfunction "SBWTDIO_SBWTDIO") (pintype "bidirectional"))
      (node (ref "U$2") (pin "2") (pinfunction "SBWTDIO_2") (pintype "bidirectional"))
    )
    (net (code "34") (name "Net-(U$5-ILIM)") (class "Default")
      (node (ref "RLIM") (pin "1") (pinfunction "1_1") (pintype "passive"))
      (node (ref "U$5") (pin "10") (pinfunction "ILIM_10") (pintype "bidirectional"))
    )
    (net (code "35") (name "Net-(U$5-VOUT)") (class "Default")
      (node (ref "COUT") (pin "1") (pinfunction "1_1") (pintype "passive"))
      (node (ref "R18") (pin "2") (pinfunction "2_2") (pintype "passive"))
      (node (ref "R19") (pin "2") (pinfunction "2_2") (pintype "passive"))
      (node (ref "R20") (pin "2") (pinfunction "2_2") (pintype "passive"))
      (node (ref "R5") (pin "2") (pinfunction "2_2") (pintype "passive"))
      (node (ref "U$5") (pin "6") (pinfunction "VOUT3_6") (pintype "bidirectional"))
      (node (ref "U$5") (pin "7") (pinfunction "VOUT2_7") (pintype "bidirectional"))
      (node (ref "U$5") (pin "8") (pinfunction "VOUT_8") (pintype "bidirectional"))
    )
    (net (code "36") (name "Net-(U$8-CD)") (class "Default")
      (node (ref "C4") (pin "1") (pinfunction "1_1") (pintype "passive"))
      (node (ref "U$8") (pin "P$4") (pinfunction "CD_P$4") (pintype "bidirectional"))
    )
    (net (code "37") (name "Net-(U$8-VC1)") (class "Default")
      (node (ref "C1") (pin "2") (pinfunction "2_2") (pintype "passive"))
      (node (ref "C2") (pin "1") (pinfunction "1_1") (pintype "passive"))
      (node (ref "R8") (pin "1") (pinfunction "1_1") (pintype "passive"))
      (node (ref "U$8") (pin "P$2") (pinfunction "VC1_P$2") (pintype "bidirectional"))
    )
    (net (code "38") (name "Net-(U$8-VC2)") (class "Default")
      (node (ref "C1") (pin "1") (pinfunction "1_1") (pintype "passive"))
      (node (ref "R7") (pin "1") (pinfunction "1_1") (pintype "passive"))
      (node (ref "U$8") (pin "P$1") (pinfunction "VC2_P$1") (pintype "bidirectional"))
    )
    (net (code "39") (name "Net-(U$8-VDD)") (class "Default")
      (node (ref "C3") (pin "1") (pinfunction "1_1") (pintype "passive"))
      (node (ref "RVD") (pin "1") (pinfunction "1_1") (pintype "passive"))
      (node (ref "U$8") (pin "P$6") (pinfunction "VDD_P$6") (pintype "bidirectional"))
    )
    (net (code "40") (name "Net-(U$10-P$+)") (class "Default")
      (node (ref "R24") (pin "1") (pinfunction "1_1") (pintype "passive"))
      (node (ref "R26") (pin "1") (pinfunction "1_1") (pintype "passive"))
      (node (ref "R27") (pin "2") (pinfunction "2_2") (pintype "passive"))
      (node (ref "TP1") (pin "TP") (pinfunction "TP_TP") (pintype "input"))
      (node (ref "U$10") (pin "2") (pinfunction "P$+_2") (pintype "bidirectional"))
      (node (ref "VR1") (pin "3") (pinfunction "CCW_3") (pintype "passive"))
    )
    (net (code "41") (name "Net-(U$10-P$ADJ)") (class "Default")
      (node (ref "R25") (pin "1") (pinfunction "1_1") (pintype "passive"))
      (node (ref "R26") (pin "2") (pinfunction "2_2") (pintype "passive"))
      (node (ref "TP4") (pin "TP") (pinfunction "TP_TP") (pintype "input"))
      (node (ref "U$10") (pin "3") (pinfunction "P$ADJ_3") (pintype "bidirectional"))
      (node (ref "VR1") (pin "2") (pinfunction "WIPER_2") (pintype "passive"))
    )
    (net (code "42") (name "unconnected-(U$1-P2.3_SPI-CS2-PadP2.4_SPI-CS2)") (class "Default")
      (node (ref "U$1") (pin "P2.4_SPI-CS2") (pinfunction "P2.3_SPI-CS2_P2.4_SPI-CS2") (pintype "bidirectional"))
    )
    (net (code "43") (name "unconnected-(U$1-PadP1.2_A2)") (class "Default")
      (node (ref "U$1") (pin "P1.2_A2") (pinfunction "P1.2_A2_P1.2_A2") (pintype "bidirectional"))
    )
    (net (code "44") (name "unconnected-(U$1-PadP1.3_A3)") (class "Default")
      (node (ref "U$1") (pin "P1.3_A3") (pinfunction "P1.3_A3_P1.3_A3") (pintype "bidirectional"))
    )
    (net (code "45") (name "unconnected-(U$1-PadP1.4_A4)") (class "Default")
      (node (ref "U$1") (pin "P1.4_A4") (pinfunction "P1.4_A4_P1.4_A4") (pintype "bidirectional"))
    )
    (net (code "46") (name "unconnected-(U$1-PadP1.5_A5)") (class "Default")
      (node (ref "U$1") (pin "P1.5_A5") (pinfunction "P1.5_A5_P1.5_A5") (pintype "bidirectional"))
    )
    (net (code "47") (name "unconnected-(U$1-PadP2.2_GPIO{slash}PWM)") (class "Default")
      (node (ref "U$1") (pin "P2.2_GPIO/PWM") (pinfunction "P2.2_GPIO/PWM_P2.2_GPIO/PWM") (pintype "bidirectional"))
    )
    (net (code "48") (name "unconnected-(U$1-PadP2.5_GPIO)") (class "Default")
      (node (ref "U$1") (pin "P2.5_GPIO") (pinfunction "P2.5_GPIO_P2.5_GPIO") (pintype "bidirectional"))
    )
    (net (code "49") (name "unconnected-(U$1-PadP2.6_GPIO{slash}PWM)") (class "Default")
      (node (ref "U$1") (pin "P2.6_GPIO/PWM") (pinfunction "P2.6_GPIO/PWM_P2.6_GPIO/PWM") (pintype "bidirectional"))
    )
    (net (code "50") (name "unconnected-(U$1-PadP2.7_SPI-CS3)") (class "Default")
      (node (ref "U$1") (pin "P2.7_SPI-CS3") (pinfunction "P2.7_SPI-CS3_P2.7_SPI-CS3") (pintype "bidirectional"))
    )
    (net (code "51") (name "unconnected-(U$1-PadP3.0_A12)") (class "Default")
      (node (ref "U$1") (pin "P3.0_A12") (pinfunction "P3.0_A12_P3.0_A12") (pintype "bidirectional"))
    )
    (net (code "52") (name "unconnected-(U$1-PadP3.1_A13)") (class "Default")
      (node (ref "U$1") (pin "P3.1_A13") (pinfunction "P3.1_A13_P3.1_A13") (pintype "bidirectional"))
    )
    (net (code "53") (name "unconnected-(U$1-PadP3.2_A14)") (class "Default")
      (node (ref "U$1") (pin "P3.2_A14") (pinfunction "P3.2_A14_P3.2_A14") (pintype "bidirectional"))
    )
    (net (code "54") (name "unconnected-(U$1-PadP3.3_A15)") (class "Default")
      (node (ref "U$1") (pin "P3.3_A15") (pinfunction "P3.3_A15_P3.3_A15") (pintype "bidirectional"))
    )
    (net (code "55") (name "unconnected-(U$1-PadP3.6_GPIO{slash}PWM)") (class "Default")
      (node (ref "U$1") (pin "P3.6_GPIO/PWM") (pinfunction "P3.6_GPIO/PWM_P3.6_GPIO/PWM") (pintype "bidirectional"))
    )
    (net (code "56") (name "unconnected-(U$1-PadP4.0_GPIO)") (class "Default")
      (node (ref "U$1") (pin "P4.0_GPIO") (pinfunction "P4.0_GPIO_P4.0_GPIO") (pintype "bidirectional"))
    )
    (net (code "57") (name "unconnected-(U$1-PadP4.1_GPIO)") (class "Default")
      (node (ref "U$1") (pin "P4.1_GPIO") (pinfunction "P4.1_GPIO_P4.1_GPIO") (pintype "bidirectional"))
    )
    (net (code "58") (name "unconnected-(U$1-PadP4.2_GPIO)") (class "Default")
      (node (ref "U$1") (pin "P4.2_GPIO") (pinfunction "P4.2_GPIO_P4.2_GPIO") (pintype "bidirectional"))
    )
    (net (code "59") (name "unconnected-(U$1-PadP4.3_GPIO)") (class "Default")
      (node (ref "U$1") (pin "P4.3_GPIO") (pinfunction "P4.3_GPIO_P4.3_GPIO") (pintype "bidirectional"))
    )
    (net (code "60") (name "unconnected-(U$1-PadP5.4_SPI-MOSI)") (class "Default")
      (node (ref "U$1") (pin "P5.4_SPI-MOSI") (pinfunction "P5.4_SPI-MOSI_P5.4_SPI-MOSI") (pintype "bidirectional"))
    )
    (net (code "61") (name "unconnected-(U$1-PadP5.5_SPI-MISO)") (class "Default")
      (node (ref "U$1") (pin "P5.5_SPI-MISO") (pinfunction "P5.5_SPI-MISO_P5.5_SPI-MISO") (pintype "bidirectional"))
    )
    (net (code "62") (name "unconnected-(U$1-PadP5.6_SPI-CLK)") (class "Default")
      (node (ref "U$1") (pin "P5.6_SPI-CLK") (pinfunction "P5.6_SPI-CLK_P5.6_SPI-CLK") (pintype "bidirectional"))
    )
    (net (code "63") (name "unconnected-(U$1-PadP7.0_I2C-SDA-2)") (class "Default")
      (node (ref "U$1") (pin "P7.0_I2C-SDA-2") (pinfunction "P7.0_I2C-SDA-2_P7.0_I2C-SDA-2") (pintype "bidirectional"))
    )
    (net (code "64") (name "unconnected-(U$1-PadP7.1_I2C-SCL-2)") (class "Default")
      (node (ref "U$1") (pin "P7.1_I2C-SCL-2") (pinfunction "P7.1_I2C-SCL-2_P7.1_I2C-SCL-2") (pintype "bidirectional"))
    )
    (net (code "65") (name "unconnected-(U$1-PadP7.3_GPIO)") (class "Default")
      (node (ref "U$1") (pin "P7.3_GPIO") (pinfunction "P7.3_GPIO_P7.3_GPIO") (pintype "bidirectional"))
    )
    (net (code "66") (name "unconnected-(U$1-PadP7.4_GPIO)") (class "Default")
      (node (ref "U$1") (pin "P7.4_GPIO") (pinfunction "P7.4_GPIO_P7.4_GPIO") (pintype "bidirectional"))
    )
    (net (code "67") (name "unconnected-(U$5-BFET-Pad9)") (class "Default")
      (node (ref "U$5") (pin "9") (pinfunction "BFET_9") (pintype "bidirectional"))
    )
    (net (code "68") (name "unconnected-(U$5-DV{slash}DT-Pad1)") (class "Default")
      (node (ref "U$5") (pin "1") (pinfunction "DV/DT_1") (pintype "bidirectional"))
    )
    (net (code "69") (name "unconnected-(U$7-ADCS2_GND-PadP$82)") (class "Default")
      (node (ref "U$7") (pin "P$82") (pinfunction "ADCS2_GND_P$82") (pintype "bidirectional"))
    )
    (net (code "70") (name "unconnected-(U$7-ADCS2_GND-PadP$84)") (class "Default")
      (node (ref "U$7") (pin "P$84") (pinfunction "ADCS2_GND_P$84") (pintype "bidirectional"))
    )
    (net (code "71") (name "unconnected-(U$7-ADCS2_VBAT-PadP$81)") (class "Default")
      (node (ref "U$7") (pin "P$81") (pinfunction "ADCS2_VBAT_P$81") (pintype "bidirectional"))
    )
    (net (code "72") (name "unconnected-(U$7-ADCS2_VBAT-PadP$83)") (class "Default")
      (node (ref "U$7") (pin "P$83") (pinfunction "ADCS2_VBAT_P$83") (pintype "bidirectional"))
    )
    (net (code "73") (name "unconnected-(U$7-BDOT_GND-PadP$86)") (class "Default")
      (node (ref "U$7") (pin "P$86") (pinfunction "BDOT_GND_P$86") (pintype "bidirectional"))
    )
    (net (code "74") (name "unconnected-(U$7-BDOT_GND-PadP$88)") (class "Default")
      (node (ref "U$7") (pin "P$88") (pinfunction "BDOT_GND_P$88") (pintype "bidirectional"))
    )
    (net (code "75") (name "unconnected-(U$7-BDOT_I2C_SCL-PadP$90)") (class "Default")
      (node (ref "U$7") (pin "P$90") (pinfunction "BDOT_I2C_SCL_P$90") (pintype "bidirectional"))
    )
    (net (code "76") (name "unconnected-(U$7-BDOT_I2C_SDA-PadP$89)") (class "Default")
      (node (ref "U$7") (pin "P$89") (pinfunction "BDOT_I2C_SDA_P$89") (pintype "bidirectional"))
    )
    (net (code "77") (name "unconnected-(U$7-BDOT_VBAT-PadP$85)") (class "Default")
      (node (ref "U$7") (pin "P$85") (pinfunction "BDOT_VBAT_P$85") (pintype "bidirectional"))
    )
    (net (code "78") (name "unconnected-(U$7-BDOT_VBAT-PadP$87)") (class "Default")
      (node (ref "U$7") (pin "P$87") (pinfunction "BDOT_VBAT_P$87") (pintype "bidirectional"))
    )
    (net (code "79") (name "unconnected-(U$7-COM1_GND-PadP$102)") (class "Default")
      (node (ref "U$7") (pin "P$102") (pinfunction "COM1_GND_P$102") (pintype "bidirectional"))
    )
    (net (code "80") (name "unconnected-(U$7-COM1_GND-PadP$104)") (class "Default")
      (node (ref "U$7") (pin "P$104") (pinfunction "COM1_GND_P$104") (pintype "bidirectional"))
    )
    (net (code "81") (name "unconnected-(U$7-COM1_VBAT-PadP$101)") (class "Default")
      (node (ref "U$7") (pin "P$101") (pinfunction "COM1_VBAT_P$101") (pintype "bidirectional"))
    )
    (net (code "82") (name "unconnected-(U$7-COM1_VBAT-PadP$103)") (class "Default")
      (node (ref "U$7") (pin "P$103") (pinfunction "COM1_VBAT_P$103") (pintype "bidirectional"))
    )
    (net (code "83") (name "unconnected-(U$7-COM2_GND-PadP$98)") (class "Default")
      (node (ref "U$7") (pin "P$98") (pinfunction "COM2_GND_P$98") (pintype "bidirectional"))
    )
    (net (code "84") (name "unconnected-(U$7-COM2_GND-PadP$100)") (class "Default")
      (node (ref "U$7") (pin "P$100") (pinfunction "COM2_GND_P$100") (pintype "bidirectional"))
    )
    (net (code "85") (name "unconnected-(U$7-COM2_VBAT-PadP$97)") (class "Default")
      (node (ref "U$7") (pin "P$97") (pinfunction "COM2_VBAT_P$97") (pintype "bidirectional"))
    )
    (net (code "86") (name "unconnected-(U$7-COM2_VBAT-PadP$99)") (class "Default")
      (node (ref "U$7") (pin "P$99") (pinfunction "COM2_VBAT_P$99") (pintype "bidirectional"))
    )
    (net (code "87") (name "unconnected-(U$7-ESTIMAT_GND-PadP$78)") (class "Default")
      (node (ref "U$7") (pin "P$78") (pinfunction "ESTIMAT_GND_P$78") (pintype "bidirectional"))
    )
    (net (code "88") (name "unconnected-(U$7-ESTIMAT_GND-PadP$80)") (class "Default")
      (node (ref "U$7") (pin "P$80") (pinfunction "ESTIMAT_GND_P$80") (pintype "bidirectional"))
    )
    (net (code "89") (name "unconnected-(U$7-ESTIMAT_I2C_SCL-PadP$70)") (class "Default")
      (node (ref "U$7") (pin "P$70") (pinfunction "ESTIMAT_I2C_SCL_P$70") (pintype "bidirectional"))
    )
    (net (code "90") (name "unconnected-(U$7-ESTIMAT_I2C_SDA-PadP$69)") (class "Default")
      (node (ref "U$7") (pin "P$69") (pinfunction "ESTIMAT_I2C_SDA_P$69") (pintype "bidirectional"))
    )
    (net (code "91") (name "unconnected-(U$7-ESTIMAT_VBAT-PadP$77)") (class "Default")
      (node (ref "U$7") (pin "P$77") (pinfunction "ESTIMAT_VBAT_P$77") (pintype "bidirectional"))
    )
    (net (code "92") (name "unconnected-(U$7-ESTIMAT_VBAT-PadP$79)") (class "Default")
      (node (ref "U$7") (pin "P$79") (pinfunction "ESTIMAT_VBAT_P$79") (pintype "bidirectional"))
    )
    (net (code "93") (name "unconnected-(U$7-MAG1_PWM-PadP$73)") (class "Default")
      (node (ref "U$7") (pin "P$73") (pinfunction "MAG1_PWM_P$73") (pintype "bidirectional"))
    )
    (net (code "94") (name "unconnected-(U$7-MAG2_PWM-PadP$74)") (class "Default")
      (node (ref "U$7") (pin "P$74") (pinfunction "MAG2_PWM_P$74") (pintype "bidirectional"))
    )
    (net (code "95") (name "unconnected-(U$7-MAG3_PWM-PadP$75)") (class "Default")
      (node (ref "U$7") (pin "P$75") (pinfunction "MAG3_PWM_P$75") (pintype "bidirectional"))
    )
    (net (code "96") (name "unconnected-(U$7-MCU_GND-PadP$46)") (class "Default")
      (node (ref "U$7") (pin "P$46") (pinfunction "MCU_GND_P$46") (pintype "bidirectional"))
    )
    (net (code "97") (name "unconnected-(U$7-MCU_GND-PadP$47)") (class "Default")
      (node (ref "U$7") (pin "P$47") (pinfunction "MCU_GND_P$47") (pintype "bidirectional"))
    )
    (net (code "98") (name "unconnected-(U$7-MCU_GND-PadP$58)") (class "Default")
      (node (ref "U$7") (pin "P$58") (pinfunction "MCU_GND_P$58") (pintype "bidirectional"))
    )
    (net (code "99") (name "unconnected-(U$7-MCU_GND-PadP$59)") (class "Default")
      (node (ref "U$7") (pin "P$59") (pinfunction "MCU_GND_P$59") (pintype "bidirectional"))
    )
    (net (code "100") (name "unconnected-(U$7-PPT_GND-PadP$1)") (class "Default")
      (node (ref "U$7") (pin "P$1") (pinfunction "PPT_GND_P$1") (pintype "bidirectional"))
    )
    (net (code "101") (name "unconnected-(U$7-PPT_GND-PadP$3)") (class "Default")
      (node (ref "U$7") (pin "P$3") (pinfunction "PPT_GND_P$3") (pintype "bidirectional"))
    )
    (net (code "102") (name "unconnected-(U$7-PPT_GND-PadP$6)") (class "Default")
      (node (ref "U$7") (pin "P$6") (pinfunction "PPT_GND_P$6") (pintype "bidirectional"))
    )
    (net (code "103") (name "unconnected-(U$7-PPT_GND-PadP$8)") (class "Default")
      (node (ref "U$7") (pin "P$8") (pinfunction "PPT_GND_P$8") (pintype "bidirectional"))
    )
    (net (code "104") (name "unconnected-(U$7-PPT_GND-PadP$9)") (class "Default")
      (node (ref "U$7") (pin "P$9") (pinfunction "PPT_GND_P$9") (pintype "bidirectional"))
    )
    (net (code "105") (name "unconnected-(U$7-PPT_GND-PadP$11)") (class "Default")
      (node (ref "U$7") (pin "P$11") (pinfunction "PPT_GND_P$11") (pintype "bidirectional"))
    )
    (net (code "106") (name "unconnected-(U$7-PPT_GND-PadP$14)") (class "Default")
      (node (ref "U$7") (pin "P$14") (pinfunction "PPT_GND_P$14") (pintype "bidirectional"))
    )
    (net (code "107") (name "unconnected-(U$7-PPT_GND-PadP$16)") (class "Default")
      (node (ref "U$7") (pin "P$16") (pinfunction "PPT_GND_P$16") (pintype "bidirectional"))
    )
    (net (code "108") (name "unconnected-(U$7-PPT_VBAT-PadP$2)") (class "Default")
      (node (ref "U$7") (pin "P$2") (pinfunction "PPT_VBAT_P$2") (pintype "bidirectional"))
    )
    (net (code "109") (name "unconnected-(U$7-PPT_VBAT-PadP$4)") (class "Default")
      (node (ref "U$7") (pin "P$4") (pinfunction "PPT_VBAT_P$4") (pintype "bidirectional"))
    )
    (net (code "110") (name "unconnected-(U$7-PPT_VBAT-PadP$5)") (class "Default")
      (node (ref "U$7") (pin "P$5") (pinfunction "PPT_VBAT_P$5") (pintype "bidirectional"))
    )
    (net (code "111") (name "unconnected-(U$7-PPT_VBAT-PadP$7)") (class "Default")
      (node (ref "U$7") (pin "P$7") (pinfunction "PPT_VBAT_P$7") (pintype "bidirectional"))
    )
    (net (code "112") (name "unconnected-(U$7-PPT_VBAT-PadP$10)") (class "Default")
      (node (ref "U$7") (pin "P$10") (pinfunction "PPT_VBAT_P$10") (pintype "bidirectional"))
    )
    (net (code "113") (name "unconnected-(U$7-PPT_VBAT-PadP$12)") (class "Default")
      (node (ref "U$7") (pin "P$12") (pinfunction "PPT_VBAT_P$12") (pintype "bidirectional"))
    )
    (net (code "114") (name "unconnected-(U$7-PPT_VBAT-PadP$13)") (class "Default")
      (node (ref "U$7") (pin "P$13") (pinfunction "PPT_VBAT_P$13") (pintype "bidirectional"))
    )
    (net (code "115") (name "unconnected-(U$7-PPT_VBAT-PadP$15)") (class "Default")
      (node (ref "U$7") (pin "P$15") (pinfunction "PPT_VBAT_P$15") (pintype "bidirectional"))
    )
    (net (code "116") (name "unconnected-(U$7-PadP$33)") (class "Default")
      (node (ref "U$7") (pin "P$33") (pinfunction "P$33_P$33") (pintype "bidirectional"))
    )
    (net (code "117") (name "unconnected-(U$7-PadP$34)") (class "Default")
      (node (ref "U$7") (pin "P$34") (pinfunction "P$34_P$34") (pintype "bidirectional"))
    )
    (net (code "118") (name "unconnected-(U$7-PadP$35)") (class "Default")
      (node (ref "U$7") (pin "P$35") (pinfunction "P$35_P$35") (pintype "bidirectional"))
    )
    (net (code "119") (name "unconnected-(U$7-PadP$36)") (class "Default")
      (node (ref "U$7") (pin "P$36") (pinfunction "P$36_P$36") (pintype "bidirectional"))
    )
    (net (code "120") (name "unconnected-(U$7-PadP$37)") (class "Default")
      (node (ref "U$7") (pin "P$37") (pinfunction "P$37_P$37") (pintype "bidirectional"))
    )
    (net (code "121") (name "unconnected-(U$7-PadP$38)") (class "Default")
      (node (ref "U$7") (pin "P$38") (pinfunction "P$38_P$38") (pintype "bidirectional"))
    )
    (net (code "122") (name "unconnected-(U$7-PadP$39)") (class "Default")
      (node (ref "U$7") (pin "P$39") (pinfunction "P$39_P$39") (pintype "bidirectional"))
    )
    (net (code "123") (name "unconnected-(U$7-PadP$40)") (class "Default")
      (node (ref "U$7") (pin "P$40") (pinfunction "P$40_P$40") (pintype "bidirectional"))
    )
    (net (code "124") (name "unconnected-(U$7-PadP$41)") (class "Default")
      (node (ref "U$7") (pin "P$41") (pinfunction "P$41_P$41") (pintype "bidirectional"))
    )
    (net (code "125") (name "unconnected-(U$7-PadP$42)") (class "Default")
      (node (ref "U$7") (pin "P$42") (pinfunction "P$42_P$42") (pintype "bidirectional"))
    )
    (net (code "126") (name "unconnected-(U$7-PadP$43)") (class "Default")
      (node (ref "U$7") (pin "P$43") (pinfunction "P$43_P$43") (pintype "bidirectional"))
    )
    (net (code "127") (name "unconnected-(U$7-PadP$44)") (class "Default")
      (node (ref "U$7") (pin "P$44") (pinfunction "P$44_P$44") (pintype "bidirectional"))
    )
    (net (code "128") (name "unconnected-(U$7-PadP$48)") (class "Default")
      (node (ref "U$7") (pin "P$48") (pinfunction "P$48_P$48") (pintype "bidirectional"))
    )
    (net (code "129") (name "unconnected-(U$7-PadP$52)") (class "Default")
      (node (ref "U$7") (pin "P$52") (pinfunction "P$52_P$52") (pintype "bidirectional"))
    )
    (net (code "130") (name "unconnected-(U$7-PadP$56)") (class "Default")
      (node (ref "U$7") (pin "P$56") (pinfunction "P$56_P$56") (pintype "bidirectional"))
    )
    (net (code "131") (name "unconnected-(U$7-PadP$60)") (class "Default")
      (node (ref "U$7") (pin "P$60") (pinfunction "P$60_P$60") (pintype "bidirectional"))
    )
    (net (code "132") (name "unconnected-(U$7-PadP$61)") (class "Default")
      (node (ref "U$7") (pin "P$61") (pinfunction "P$61_P$61") (pintype "bidirectional"))
    )
    (net (code "133") (name "unconnected-(U$7-PadP$62)") (class "Default")
      (node (ref "U$7") (pin "P$62") (pinfunction "P$62_P$62") (pintype "bidirectional"))
    )
    (net (code "134") (name "unconnected-(U$7-PadP$63)") (class "Default")
      (node (ref "U$7") (pin "P$63") (pinfunction "P$63_P$63") (pintype "bidirectional"))
    )
    (net (code "135") (name "unconnected-(U$7-PadP$64)") (class "Default")
      (node (ref "U$7") (pin "P$64") (pinfunction "P$64_P$64") (pintype "bidirectional"))
    )
    (net (code "136") (name "unconnected-(U$7-PadP$65)") (class "Default")
      (node (ref "U$7") (pin "P$65") (pinfunction "P$65_P$65") (pintype "bidirectional"))
    )
    (net (code "137") (name "unconnected-(U$7-PadP$66)") (class "Default")
      (node (ref "U$7") (pin "P$66") (pinfunction "P$66_P$66") (pintype "bidirectional"))
    )
    (net (code "138") (name "unconnected-(U$7-PadP$67)") (class "Default")
      (node (ref "U$7") (pin "P$67") (pinfunction "P$67_P$67") (pintype "bidirectional"))
    )
    (net (code "139") (name "unconnected-(U$7-PadP$68)") (class "Default")
      (node (ref "U$7") (pin "P$68") (pinfunction "P$68_P$68") (pintype "bidirectional"))
    )
    (net (code "140") (name "unconnected-(U$7-PadP$71)") (class "Default")
      (node (ref "U$7") (pin "P$71") (pinfunction "P$71_P$71") (pintype "bidirectional"))
    )
    (net (code "141") (name "unconnected-(U$7-PadP$72)") (class "Default")
      (node (ref "U$7") (pin "P$72") (pinfunction "P$72_P$72") (pintype "bidirectional"))
    )
    (net (code "142") (name "unconnected-(U$7-PadP$76)") (class "Default")
      (node (ref "U$7") (pin "P$76") (pinfunction "P$76_P$76") (pintype "bidirectional"))
    )
    (net (code "143") (name "unconnected-(U$7-PadP$91)") (class "Default")
      (node (ref "U$7") (pin "P$91") (pinfunction "P$91_P$91") (pintype "bidirectional"))
    )
    (net (code "144") (name "unconnected-(U$7-PadP$92)") (class "Default")
      (node (ref "U$7") (pin "P$92") (pinfunction "P$92_P$92") (pintype "bidirectional"))
    )
    (net (code "145") (name "unconnected-(U$7-PadP$95)") (class "Default")
      (node (ref "U$7") (pin "P$95") (pinfunction "P$95_P$95") (pintype "bidirectional"))
    )
    (net (code "146") (name "unconnected-(U$7-PadP$96)") (class "Default")
      (node (ref "U$7") (pin "P$96") (pinfunction "P$96_P$96") (pintype "bidirectional"))
    )
    (net (code "147") (name "unconnected-(U$7-RAHS_GND-PadP$94)") (class "Default")
      (node (ref "U$7") (pin "P$94") (pinfunction "RAHS_GND_P$94") (pintype "bidirectional"))
    )
    (net (code "148") (name "unconnected-(U$7-RAHS_VBAT-PadP$93)") (class "Default")
      (node (ref "U$7") (pin "P$93") (pinfunction "RAHS_VBAT_P$93") (pintype "bidirectional"))
    )
  )
)
